# PIC_Microcontroller.net
KiCad netlist of a schematic drawn in Altium Designer
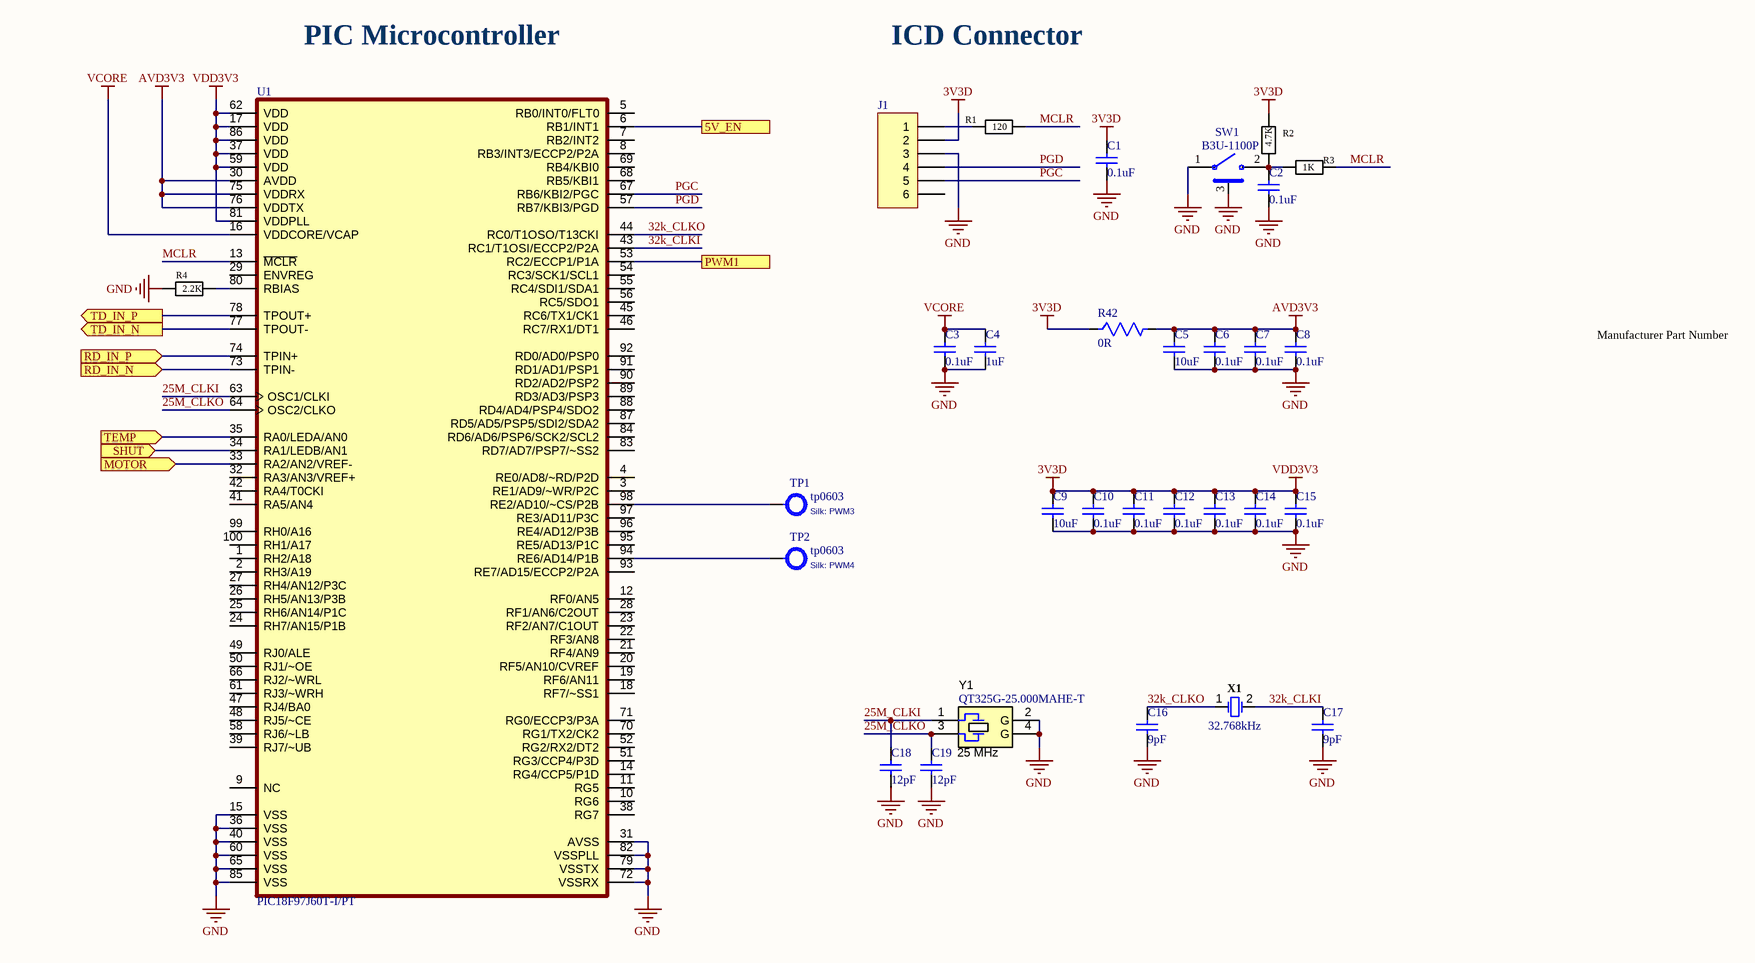
[diagram p0: PIC Microcontroller.SchDoc]

(export (version "E")
  (design (tool "Eeschema 10.0.6"))
  (components
    (comp (ref "C1")
      (value "0.1uF")
      (footprint "CAPC1005X61USR")
      (description "CAP CER 0.1UF 50V X7R 0402")
      (fields
        (field (name "MANUFACTURER") "TDK Corporation")
        (field (name "MANUFACTURER PART NUMBER") "CGA2B3X7R1H104K050BB")
      )
      (libsource (lib "AA-Design-Challenge") (part "Cap"))
    )
    (comp (ref "C2")
      (value "0.1uF")
      (footprint "CAPC1005X61USR")
      (description "CAP CER 0.1UF 50V X7R 0402")
      (fields
        (field (name "MANUFACTURER") "TDK Corporation")
        (field (name "MANUFACTURER PART NUMBER") "CGA2B3X7R1H104K050BB")
      )
      (libsource (lib "AA-Design-Challenge") (part "Cap"))
    )
    (comp (ref "C3")
      (value "0.1uF")
      (footprint "CAPC1005X61USR")
      (description "CAP CER 0.1UF 50V X7R 0402")
      (fields
        (field (name "MANUFACTURER") "TDK Corporation")
        (field (name "MANUFACTURER PART NUMBER") "CGA2B3X7R1H104K050BB")
      )
      (libsource (lib "AA-Design-Challenge") (part "Cap"))
    )
    (comp (ref "C4")
      (value "1uF")
      (footprint "CAPC1005X61USR")
      (description "CAP CER 1UF 16V X5R 0402")
      (fields
        (field (name "MANUFACTURER") "Samsung Electro-Mechanics")
        (field (name "MANUFACTURER PART NUMBER") "CL05A105KO5NNNC")
      )
      (libsource (lib "AA-Design-Challenge") (part "Cap"))
    )
    (comp (ref "C5")
      (value "10uF")
      (footprint "CAPC1005X61USR")
      (description "CAP CER 10UF 10V X5R 0402")
      (fields
        (field (name "MANUFACTURER") "Samsung Electro-Mechanics")
        (field (name "MANUFACTURER PART NUMBER") "CL05A106MP8NUB8")
      )
      (libsource (lib "AA-Design-Challenge") (part "Cap"))
    )
    (comp (ref "C6")
      (value "0.1uF")
      (footprint "CAPC1005X61USR")
      (description "CAP CER 0.1UF 50V X7R 0402")
      (fields
        (field (name "MANUFACTURER") "TDK Corporation")
        (field (name "MANUFACTURER PART NUMBER") "CGA2B3X7R1H104K050BB")
      )
      (libsource (lib "AA-Design-Challenge") (part "Cap"))
    )
    (comp (ref "C7")
      (value "0.1uF")
      (footprint "CAPC1005X61USR")
      (description "CAP CER 0.1UF 50V X7R 0402")
      (fields
        (field (name "MANUFACTURER") "TDK Corporation")
        (field (name "MANUFACTURER PART NUMBER") "CGA2B3X7R1H104K050BB")
      )
      (libsource (lib "AA-Design-Challenge") (part "Cap"))
    )
    (comp (ref "C8")
      (value "0.1uF")
      (footprint "CAPC1005X61USR")
      (description "CAP CER 0.1UF 50V X7R 0402")
      (fields
        (field (name "MANUFACTURER") "TDK Corporation")
        (field (name "MANUFACTURER PART NUMBER") "CGA2B3X7R1H104K050BB")
      )
      (libsource (lib "AA-Design-Challenge") (part "Cap"))
    )
    (comp (ref "C9")
      (value "10uF")
      (footprint "CAPC1005X61USR")
      (description "CAP CER 10UF 10V X5R 0402")
      (fields
        (field (name "MANUFACTURER") "Samsung Electro-Mechanics")
        (field (name "MANUFACTURER PART NUMBER") "CL05A106MP8NUB8")
      )
      (libsource (lib "AA-Design-Challenge") (part "Cap"))
    )
    (comp (ref "C10")
      (value "0.1uF")
      (footprint "CAPC1005X61USR")
      (description "CAP CER 0.1UF 50V X7R 0402")
      (fields
        (field (name "MANUFACTURER") "TDK Corporation")
        (field (name "MANUFACTURER PART NUMBER") "CGA2B3X7R1H104K050BB")
      )
      (libsource (lib "AA-Design-Challenge") (part "Cap"))
    )
    (comp (ref "C11")
      (value "0.1uF")
      (footprint "CAPC1005X61USR")
      (description "CAP CER 0.1UF 50V X7R 0402")
      (fields
        (field (name "MANUFACTURER") "TDK Corporation")
        (field (name "MANUFACTURER PART NUMBER") "CGA2B3X7R1H104K050BB")
      )
      (libsource (lib "AA-Design-Challenge") (part "Cap"))
    )
    (comp (ref "C12")
      (value "0.1uF")
      (footprint "CAPC1005X61USR")
      (description "CAP CER 0.1UF 50V X7R 0402")
      (fields
        (field (name "MANUFACTURER") "TDK Corporation")
        (field (name "MANUFACTURER PART NUMBER") "CGA2B3X7R1H104K050BB")
      )
      (libsource (lib "AA-Design-Challenge") (part "Cap"))
    )
    (comp (ref "C13")
      (value "0.1uF")
      (footprint "CAPC1005X61USR")
      (description "CAP CER 0.1UF 50V X7R 0402")
      (fields
        (field (name "MANUFACTURER") "TDK Corporation")
        (field (name "MANUFACTURER PART NUMBER") "CGA2B3X7R1H104K050BB")
      )
      (libsource (lib "AA-Design-Challenge") (part "Cap"))
    )
    (comp (ref "C14")
      (value "0.1uF")
      (footprint "CAPC1005X61USR")
      (description "CAP CER 0.1UF 50V X7R 0402")
      (fields
        (field (name "MANUFACTURER") "TDK Corporation")
        (field (name "MANUFACTURER PART NUMBER") "CGA2B3X7R1H104K050BB")
      )
      (libsource (lib "AA-Design-Challenge") (part "Cap"))
    )
    (comp (ref "C15")
      (value "0.1uF")
      (footprint "CAPC1005X61USR")
      (description "CAP CER 0.1UF 50V X7R 0402")
      (fields
        (field (name "MANUFACTURER") "TDK Corporation")
        (field (name "MANUFACTURER PART NUMBER") "CGA2B3X7R1H104K050BB")
      )
      (libsource (lib "AA-Design-Challenge") (part "Cap"))
    )
    (comp (ref "C16")
      (value "9pF")
      (footprint "CAPC1005X61USR")
      (description "CAP CER 9PF 50V C0G/NPO 0402")
      (fields
        (field (name "MANUFACTURER") "Yageo")
        (field (name "MANUFACTURER PART NUMBER") "CC0402BRNPO9BN9R0")
      )
      (libsource (lib "AA-Design-Challenge") (part "Cap"))
    )
    (comp (ref "C17")
      (value "9pF")
      (footprint "CAPC1005X61USR")
      (description "CAP CER 9PF 50V C0G/NPO 0402")
      (fields
        (field (name "MANUFACTURER") "Yageo")
        (field (name "MANUFACTURER PART NUMBER") "CC0402BRNPO9BN9R0")
      )
      (libsource (lib "AA-Design-Challenge") (part "Cap"))
    )
    (comp (ref "C18")
      (value "12pF")
      (footprint "CAPC1005X61USR")
      (description "CAP CER 12PF 50V C0G 0402")
      (fields
        (field (name "MANUFACTURER") "TDK Corporation")
        (field (name "MANUFACTURER PART NUMBER") "CGA2B2C0G1H120J050BA")
      )
      (libsource (lib "AA-Design-Challenge") (part "Cap"))
    )
    (comp (ref "C19")
      (value "12pF")
      (footprint "CAPC1005X61USR")
      (description "CAP CER 12PF 50V C0G 0402")
      (fields
        (field (name "MANUFACTURER") "TDK Corporation")
        (field (name "MANUFACTURER PART NUMBER") "CGA2B2C0G1H120J050BA")
      )
      (libsource (lib "AA-Design-Challenge") (part "Cap"))
    )
    (comp (ref "J1")
      (value "Header 6")
      (footprint "HDR1X6")
      (description "Header, 6-Pin")
      (fields (field (name "PUBLISHER") "Altium Limited"))
      (libsource (lib "AA-Design-Challenge") (part "Header 6"))
    )
    (comp (ref "R1")
      (value "120")
      (footprint "RESC1005X40USR")
      (description "RES SMD 120 OHM 1% 1/16W 0402")
      (fields
        (field (name "MANUFACTURER") "Yageo")
        (field (name "MANUFACTURER PART NUMBER") "RC0402FR-07120RL")
      )
      (libsource (lib "AA-Design-Challenge") (part "R"))
    )
    (comp (ref "R2")
      (value "4.7K")
      (footprint "RESC1005X40USR")
      (description "RES SMD 4.7K OHM 1% 1/16W 0402")
      (fields
        (field (name "MANUFACTURER") "Yageo")
        (field (name "MANUFACTURER PART NUMBER") "RC0402FR-074K7L")
      )
      (libsource (lib "") (part "R_1"))
    )
    (comp (ref "R3")
      (value "1K")
      (footprint "RESC1005X40USR")
      (description "RES SMD 1K OHM 1% 1/16W 0402")
      (fields
        (field (name "MANUFACTURER") "Yageo")
        (field (name "MANUFACTURER PART NUMBER") "RC0402FR-071KL")
      )
      (libsource (lib "AA-Design-Challenge") (part "R"))
    )
    (comp (ref "R4")
      (value "2.2K")
      (footprint "RESC1005X40USR")
      (description "RES SMD 2.2K OHM 1% 1/16W 0402")
      (fields
        (field (name "MANUFACTURER") "Yageo")
        (field (name "MANUFACTURER PART NUMBER") "RC0402FR-072K2L")
      )
      (libsource (lib "AA-Design-Challenge") (part "R"))
    )
    (comp (ref "R42")
      (value "0R")
      (footprint "R_0603")
      (description "Fixed Resistor, Metal Glaze/thick Film, 0.1W, 0ohm, Surface Mount, 0603")
      (fields
        (field (name "MANUFACTURER") "Yageo")
        (field (name "MANUFACTURER PART NUMBER") "RC0603FR-070RL")
      )
      (libsource (lib "OP_Library") (part "Res 0R 1/10W 0603"))
    )
    (comp (ref "SW1")
      (value "B3U-1100P")
      (footprint "SW_B3U-1100P")
      (description "SWITCH TACTILE SPST-NO 0.05A 12V")
      (fields (field (name "MANUFACTURER") "Omron"))
      (libsource (lib "AA-Design-Challenge") (part "B3U-1100P"))
    )
    (comp (ref "TP1")
      (value "tp0603")
      (footprint "TP 1mm")
      (fields (field (name "SILK") "PWM3") (field (name "PART NUMBER") "4001364"))
      (libsource (lib "AA-Design-Challenge") (part "Testpkt0603"))
    )
    (comp (ref "TP2")
      (value "tp0603")
      (footprint "TP 1mm")
      (fields (field (name "SILK") "PWM4") (field (name "PART NUMBER") "4001364"))
      (libsource (lib "AA-Design-Challenge") (part "Testpkt0603"))
    )
    (comp (ref "U1")
      (value "PIC18F97J60T-I/PT")
      (footprint "QFP40P1400X1400X120-100N")
      (description "IC MCU 8BIT 128KB FLASH 100TQFP (12x12)")
      (fields
        (field (name "DIGI-KEY PART NUMBER") "PIC18F97J60T-I/PTTR-ND")
        (field (name "MANUFACTURER") "Microchip")
      )
      (libsource (lib "AA-Design-Challenge") (part "PIC18F97J60T-I/PT"))
    )
    (comp (ref "X1")
      (value "32.768kHz")
      (footprint "XTAL_3215")
      (description "CRYSTAL 32.7680KHZ 9PF SMD")
      (fields
        (field (name "MANUFACTURER") "EPSON")
        (field (name "MANUFACTURER PART NUMBER") "FC-135 32.7680KA-AC0")
      )
      (libsource (lib "AA-Design-Challenge") (part "XTAL-1-2-2"))
    )
    (comp (ref "Y1")
      (value "QT325G-25.000MAHE-T")
      (footprint "XTAL_3225")
      (description "CRYSTAL 25.0000MHZ 12PF SMD")
      (fields (field (name "FREQUENCY_FIXED") "25 MHz") (field (name "MANUFACTURER") "QST"))
      (libsource (lib "AA-Design-Challenge") (part "ABM8AIG-25.000MHZ-12-2Z-T3"))
    )
  )
  (nets
    (net (code "1") (name "/5V_EN") (class "Default")
      (node (ref "U1") (pin "6") (pinfunction "RB1/INT1_6") (pintype "passive"))
    )
    (net (code "2") (name "/25M_CLKI") (class "Default")
      (node (ref "C18") (pin "1") (pinfunction "1_1") (pintype "passive"))
      (node (ref "U1") (pin "63") (pinfunction "OSC1/CLKI_63") (pintype "passive"))
      (node (ref "Y1") (pin "1") (pinfunction "1_1") (pintype "passive"))
    )
    (net (code "3") (name "/25M_CLKO") (class "Default")
      (node (ref "C19") (pin "1") (pinfunction "1_1") (pintype "passive"))
      (node (ref "U1") (pin "64") (pinfunction "OSC2/CLKO_64") (pintype "passive"))
      (node (ref "Y1") (pin "3") (pinfunction "3_3") (pintype "passive"))
    )
    (net (code "4") (name "/32k_CLKI") (class "Default")
      (node (ref "C17") (pin "1") (pinfunction "1_1") (pintype "passive"))
      (node (ref "U1") (pin "43") (pinfunction "RC1/T1OSI/ECCP2/P2A_43") (pintype "passive"))
      (node (ref "X1") (pin "2") (pinfunction "2_2") (pintype "passive"))
    )
    (net (code "5") (name "/32k_CLKO") (class "Default")
      (node (ref "C16") (pin "1") (pinfunction "1_1") (pintype "passive"))
      (node (ref "U1") (pin "44") (pinfunction "RC0/T1OSO/T13CKI_44") (pintype "passive"))
      (node (ref "X1") (pin "1") (pinfunction "1_1") (pintype "passive"))
    )
    (net (code "6") (name "/MCLR") (class "Default")
      (node (ref "R1") (pin "2") (pintype "passive"))
      (node (ref "R3") (pin "2") (pintype "passive"))
      (node (ref "U1") (pin "13") (pinfunction "~{MCLR}_13") (pintype "passive"))
    )
    (net (code "7") (name "/MOTOR") (class "Default")
      (node (ref "U1") (pin "33") (pinfunction "RA2/AN2/VREF-_33") (pintype "passive"))
    )
    (net (code "8") (name "/PGC") (class "Default")
      (node (ref "J1") (pin "5") (pinfunction "5_5") (pintype "passive"))
      (node (ref "U1") (pin "67") (pinfunction "RB6/KBI2/PGC_67") (pintype "passive"))
    )
    (net (code "9") (name "/PGD") (class "Default")
      (node (ref "J1") (pin "4") (pinfunction "4_4") (pintype "passive"))
      (node (ref "U1") (pin "57") (pinfunction "RB7/KBI3/PGD_57") (pintype "passive"))
    )
    (net (code "10") (name "/PWM1") (class "Default")
      (node (ref "U1") (pin "53") (pinfunction "RC2/ECCP1/P1A_53") (pintype "passive"))
    )
    (net (code "11") (name "/RD_IN_N") (class "Default")
      (node (ref "U1") (pin "73") (pinfunction "TPIN-_73") (pintype "passive"))
    )
    (net (code "12") (name "/RD_IN_P") (class "Default")
      (node (ref "U1") (pin "74") (pinfunction "TPIN+_74") (pintype "passive"))
    )
    (net (code "13") (name "/SHUT") (class "Default")
      (node (ref "U1") (pin "34") (pinfunction "RA1/LEDB/AN1_34") (pintype "passive"))
    )
    (net (code "14") (name "/TD_IN_N") (class "Default")
      (node (ref "U1") (pin "77") (pinfunction "TPOUT-_77") (pintype "passive"))
    )
    (net (code "15") (name "/TD_IN_P") (class "Default")
      (node (ref "U1") (pin "78") (pinfunction "TPOUT+_78") (pintype "passive"))
    )
    (net (code "16") (name "/TEMP") (class "Default")
      (node (ref "U1") (pin "35") (pinfunction "RA0/LEDA/AN0_35") (pintype "passive"))
    )
    (net (code "17") (name "3V3D") (class "Default")
      (node (ref "C1") (pin "1") (pinfunction "1_1") (pintype "passive"))
      (node (ref "C10") (pin "1") (pinfunction "1_1") (pintype "passive"))
      (node (ref "C11") (pin "1") (pinfunction "1_1") (pintype "passive"))
      (node (ref "C12") (pin "1") (pinfunction "1_1") (pintype "passive"))
      (node (ref "C13") (pin "1") (pinfunction "1_1") (pintype "passive"))
      (node (ref "C14") (pin "1") (pinfunction "1_1") (pintype "passive"))
      (node (ref "C15") (pin "1") (pinfunction "1_1") (pintype "passive"))
      (node (ref "C9") (pin "1") (pinfunction "1_1") (pintype "passive"))
      (node (ref "J1") (pin "2") (pinfunction "2_2") (pintype "passive"))
      (node (ref "R2") (pin "1") (pintype "passive"))
      (node (ref "R42") (pin "1") (pinfunction "1_1") (pintype "passive"))
      (node (ref "U1") (pin "17") (pinfunction "VDD_17") (pintype "passive"))
      (node (ref "U1") (pin "37") (pinfunction "VDD_37") (pintype "passive"))
      (node (ref "U1") (pin "59") (pinfunction "VDD_59") (pintype "passive"))
      (node (ref "U1") (pin "62") (pinfunction "VDD_62") (pintype "passive"))
      (node (ref "U1") (pin "81") (pinfunction "VDDPLL_81") (pintype "passive"))
      (node (ref "U1") (pin "86") (pinfunction "VDD_86") (pintype "passive"))
    )
    (net (code "18") (name "AVD3V3") (class "Default")
      (node (ref "C5") (pin "1") (pinfunction "1_1") (pintype "passive"))
      (node (ref "C6") (pin "1") (pinfunction "1_1") (pintype "passive"))
      (node (ref "C7") (pin "1") (pinfunction "1_1") (pintype "passive"))
      (node (ref "C8") (pin "1") (pinfunction "1_1") (pintype "passive"))
      (node (ref "R42") (pin "2") (pinfunction "2_2") (pintype "passive"))
      (node (ref "U1") (pin "30") (pinfunction "AVDD_30") (pintype "passive"))
      (node (ref "U1") (pin "75") (pinfunction "VDDRX_75") (pintype "passive"))
      (node (ref "U1") (pin "76") (pinfunction "VDDTX_76") (pintype "passive"))
    )
    (net (code "19") (name "GND") (class "Default")
      (node (ref "C1") (pin "2") (pinfunction "2_2") (pintype "passive"))
      (node (ref "C10") (pin "2") (pinfunction "2_2") (pintype "passive"))
      (node (ref "C11") (pin "2") (pinfunction "2_2") (pintype "passive"))
      (node (ref "C12") (pin "2") (pinfunction "2_2") (pintype "passive"))
      (node (ref "C13") (pin "2") (pinfunction "2_2") (pintype "passive"))
      (node (ref "C14") (pin "2") (pinfunction "2_2") (pintype "passive"))
      (node (ref "C15") (pin "2") (pinfunction "2_2") (pintype "passive"))
      (node (ref "C16") (pin "2") (pinfunction "2_2") (pintype "passive"))
      (node (ref "C17") (pin "2") (pinfunction "2_2") (pintype "passive"))
      (node (ref "C18") (pin "2") (pinfunction "2_2") (pintype "passive"))
      (node (ref "C19") (pin "2") (pinfunction "2_2") (pintype "passive"))
      (node (ref "C2") (pin "2") (pinfunction "2_2") (pintype "passive"))
      (node (ref "C3") (pin "2") (pinfunction "2_2") (pintype "passive"))
      (node (ref "C4") (pin "1") (pinfunction "1_1") (pintype "passive"))
      (node (ref "C5") (pin "2") (pinfunction "2_2") (pintype "passive"))
      (node (ref "C6") (pin "2") (pinfunction "2_2") (pintype "passive"))
      (node (ref "C7") (pin "2") (pinfunction "2_2") (pintype "passive"))
      (node (ref "C8") (pin "2") (pinfunction "2_2") (pintype "passive"))
      (node (ref "C9") (pin "2") (pinfunction "2_2") (pintype "passive"))
      (node (ref "J1") (pin "3") (pinfunction "3_3") (pintype "passive"))
      (node (ref "R4") (pin "1") (pintype "passive"))
      (node (ref "SW1") (pin "1") (pinfunction "1_1") (pintype "passive"))
      (node (ref "SW1") (pin "3") (pinfunction "3_3") (pintype "passive"))
      (node (ref "U1") (pin "15") (pinfunction "VSS_15") (pintype "passive"))
      (node (ref "U1") (pin "31") (pinfunction "AVSS_31") (pintype "passive"))
      (node (ref "U1") (pin "36") (pinfunction "VSS_36") (pintype "passive"))
      (node (ref "U1") (pin "40") (pinfunction "VSS_40") (pintype "passive"))
      (node (ref "U1") (pin "60") (pinfunction "VSS_60") (pintype "passive"))
      (node (ref "U1") (pin "65") (pinfunction "VSS_65") (pintype "passive"))
      (node (ref "U1") (pin "72") (pinfunction "VSSRX_72") (pintype "passive"))
      (node (ref "U1") (pin "79") (pinfunction "VSSTX_79") (pintype "passive"))
      (node (ref "U1") (pin "82") (pinfunction "VSSPLL_82") (pintype "passive"))
      (node (ref "U1") (pin "85") (pinfunction "VSS_85") (pintype "passive"))
      (node (ref "Y1") (pin "2") (pinfunction "GND_2") (pintype "power_in"))
      (node (ref "Y1") (pin "4") (pinfunction "GND_4") (pintype "power_in"))
    )
    (net (code "20") (name "Net-(C2-Pad1)") (class "Default")
      (node (ref "C2") (pin "1") (pinfunction "1_1") (pintype "passive"))
      (node (ref "R2") (pin "2") (pintype "passive"))
      (node (ref "R3") (pin "1") (pintype "passive"))
      (node (ref "SW1") (pin "2") (pinfunction "2_2") (pintype "passive"))
    )
    (net (code "21") (name "Net-(J1-Pad1)") (class "Default")
      (node (ref "J1") (pin "1") (pinfunction "1_1") (pintype "passive"))
      (node (ref "R1") (pin "1") (pintype "passive"))
    )
    (net (code "22") (name "Net-(U1-RBIAS)") (class "Default")
      (node (ref "R4") (pin "2") (pintype "passive"))
      (node (ref "U1") (pin "80") (pinfunction "RBIAS_80") (pintype "passive"))
    )
    (net (code "23") (name "Net-(U1-RE2{slash}AD10{slash}~CS{slash}P2B)") (class "Default")
      (node (ref "TP1") (pin "1") (pinfunction "1_1") (pintype "passive"))
      (node (ref "U1") (pin "98") (pinfunction "RE2/AD10/~CS/P2B_98") (pintype "passive"))
    )
    (net (code "24") (name "Net-(U1-RE6{slash}AD14{slash}P1B)") (class "Default")
      (node (ref "TP2") (pin "1") (pinfunction "1_1") (pintype "passive"))
      (node (ref "U1") (pin "94") (pinfunction "RE6/AD14/P1B_94") (pintype "passive"))
    )
    (net (code "25") (name "VCORE") (class "Default")
      (node (ref "C3") (pin "1") (pinfunction "1_1") (pintype "passive"))
      (node (ref "C4") (pin "2") (pinfunction "2_2") (pintype "passive"))
      (node (ref "U1") (pin "16") (pinfunction "VDDCORE/VCAP_16") (pintype "passive"))
    )
    (net (code "26") (name "unconnected-(J1-Pad6)") (class "Default")
      (node (ref "J1") (pin "6") (pinfunction "6_6") (pintype "passive"))
    )
    (net (code "27") (name "unconnected-(U1-ENVREG-Pad29)") (class "Default")
      (node (ref "U1") (pin "29") (pinfunction "ENVREG_29") (pintype "passive"))
    )
    (net (code "28") (name "unconnected-(U1-NC-Pad9)") (class "Default")
      (node (ref "U1") (pin "9") (pinfunction "NC_9") (pintype "passive"))
    )
    (net (code "29") (name "unconnected-(U1-RA3{slash}AN3{slash}VREF+-Pad32)") (class "Default")
      (node (ref "U1") (pin "32") (pinfunction "RA3/AN3/VREF+_32") (pintype "passive"))
    )
    (net (code "30") (name "unconnected-(U1-RA4{slash}T0CKI-Pad42)") (class "Default")
      (node (ref "U1") (pin "42") (pinfunction "RA4/T0CKI_42") (pintype "passive"))
    )
    (net (code "31") (name "unconnected-(U1-RA5{slash}AN4-Pad41)") (class "Default")
      (node (ref "U1") (pin "41") (pinfunction "RA5/AN4_41") (pintype "passive"))
    )
    (net (code "32") (name "unconnected-(U1-RB0{slash}INT0{slash}FLT0-Pad5)") (class "Default")
      (node (ref "U1") (pin "5") (pinfunction "RB0/INT0/FLT0_5") (pintype "passive"))
    )
    (net (code "33") (name "unconnected-(U1-RB2{slash}INT2-Pad7)") (class "Default")
      (node (ref "U1") (pin "7") (pinfunction "RB2/INT2_7") (pintype "passive"))
    )
    (net (code "34") (name "unconnected-(U1-RB3{slash}INT3{slash}ECCP2{slash}P2A-Pad8)") (class "Default")
      (node (ref "U1") (pin "8") (pinfunction "RB3/INT3/ECCP2/P2A_8") (pintype "passive"))
    )
    (net (code "35") (name "unconnected-(U1-RB4{slash}KBI0-Pad69)") (class "Default")
      (node (ref "U1") (pin "69") (pinfunction "RB4/KBI0_69") (pintype "passive"))
    )
    (net (code "36") (name "unconnected-(U1-RB5{slash}KBI1-Pad68)") (class "Default")
      (node (ref "U1") (pin "68") (pinfunction "RB5/KBI1_68") (pintype "passive"))
    )
    (net (code "37") (name "unconnected-(U1-RC3{slash}SCK1{slash}SCL1-Pad54)") (class "Default")
      (node (ref "U1") (pin "54") (pinfunction "RC3/SCK1/SCL1_54") (pintype "passive"))
    )
    (net (code "38") (name "unconnected-(U1-RC4{slash}SDI1{slash}SDA1-Pad55)") (class "Default")
      (node (ref "U1") (pin "55") (pinfunction "RC4/SDI1/SDA1_55") (pintype "passive"))
    )
    (net (code "39") (name "unconnected-(U1-RC5{slash}SDO1-Pad56)") (class "Default")
      (node (ref "U1") (pin "56") (pinfunction "RC5/SDO1_56") (pintype "passive"))
    )
    (net (code "40") (name "unconnected-(U1-RC6{slash}TX1{slash}CK1-Pad45)") (class "Default")
      (node (ref "U1") (pin "45") (pinfunction "RC6/TX1/CK1_45") (pintype "passive"))
    )
    (net (code "41") (name "unconnected-(U1-RC7{slash}RX1{slash}DT1-Pad46)") (class "Default")
      (node (ref "U1") (pin "46") (pinfunction "RC7/RX1/DT1_46") (pintype "passive"))
    )
    (net (code "42") (name "unconnected-(U1-RD0{slash}AD0{slash}PSP0-Pad92)") (class "Default")
      (node (ref "U1") (pin "92") (pinfunction "RD0/AD0/PSP0_92") (pintype "passive"))
    )
    (net (code "43") (name "unconnected-(U1-RD1{slash}AD1{slash}PSP1-Pad91)") (class "Default")
      (node (ref "U1") (pin "91") (pinfunction "RD1/AD1/PSP1_91") (pintype "passive"))
    )
    (net (code "44") (name "unconnected-(U1-RD2{slash}AD2{slash}PSP2-Pad90)") (class "Default")
      (node (ref "U1") (pin "90") (pinfunction "RD2/AD2/PSP2_90") (pintype "passive"))
    )
    (net (code "45") (name "unconnected-(U1-RD3{slash}AD3{slash}PSP3-Pad89)") (class "Default")
      (node (ref "U1") (pin "89") (pinfunction "RD3/AD3/PSP3_89") (pintype "passive"))
    )
    (net (code "46") (name "unconnected-(U1-RD4{slash}AD4{slash}PSP4{slash}SDO2-Pad88)") (class "Default")
      (node (ref "U1") (pin "88") (pinfunction "RD4/AD4/PSP4/SDO2_88") (pintype "passive"))
    )
    (net (code "47") (name "unconnected-(U1-RD5{slash}AD5{slash}PSP5{slash}SDI2{slash}SDA2-Pad87)") (class "Default")
      (node (ref "U1") (pin "87") (pinfunction "RD5/AD5/PSP5/SDI2/SDA2_87") (pintype "passive"))
    )
    (net (code "48") (name "unconnected-(U1-RD6{slash}AD6{slash}PSP6{slash}SCK2{slash}SCL2-Pad84)") (class "Default")
      (node (ref "U1") (pin "84") (pinfunction "RD6/AD6/PSP6/SCK2/SCL2_84") (pintype "passive"))
    )
    (net (code "49") (name "unconnected-(U1-RD7{slash}AD7{slash}PSP7{slash}~SS2-Pad83)") (class "Default")
      (node (ref "U1") (pin "83") (pinfunction "RD7/AD7/PSP7/~SS2_83") (pintype "passive"))
    )
    (net (code "50") (name "unconnected-(U1-RE0{slash}AD8{slash}~RD{slash}P2D-Pad4)") (class "Default")
      (node (ref "U1") (pin "4") (pinfunction "RE0/AD8/~RD/P2D_4") (pintype "passive"))
    )
    (net (code "51") (name "unconnected-(U1-RE1{slash}AD9{slash}~WR{slash}P2C-Pad3)") (class "Default")
      (node (ref "U1") (pin "3") (pinfunction "RE1/AD9/~WR/P2C_3") (pintype "passive"))
    )
    (net (code "52") (name "unconnected-(U1-RE3{slash}AD11{slash}P3C-Pad97)") (class "Default")
      (node (ref "U1") (pin "97") (pinfunction "RE3/AD11/P3C_97") (pintype "passive"))
    )
    (net (code "53") (name "unconnected-(U1-RE4{slash}AD12{slash}P3B-Pad96)") (class "Default")
      (node (ref "U1") (pin "96") (pinfunction "RE4/AD12/P3B_96") (pintype "passive"))
    )
    (net (code "54") (name "unconnected-(U1-RE5{slash}AD13{slash}P1C-Pad95)") (class "Default")
      (node (ref "U1") (pin "95") (pinfunction "RE5/AD13/P1C_95") (pintype "passive"))
    )
    (net (code "55") (name "unconnected-(U1-RE7{slash}AD15{slash}ECCP2{slash}P2A-Pad93)") (class "Default")
      (node (ref "U1") (pin "93") (pinfunction "RE7/AD15/ECCP2/P2A_93") (pintype "passive"))
    )
    (net (code "56") (name "unconnected-(U1-RF0{slash}AN5-Pad12)") (class "Default")
      (node (ref "U1") (pin "12") (pinfunction "RF0/AN5_12") (pintype "passive"))
    )
    (net (code "57") (name "unconnected-(U1-RF1{slash}AN6{slash}C2OUT-Pad28)") (class "Default")
      (node (ref "U1") (pin "28") (pinfunction "RF1/AN6/C2OUT_28") (pintype "passive"))
    )
    (net (code "58") (name "unconnected-(U1-RF2{slash}AN7{slash}C1OUT-Pad23)") (class "Default")
      (node (ref "U1") (pin "23") (pinfunction "RF2/AN7/C1OUT_23") (pintype "passive"))
    )
    (net (code "59") (name "unconnected-(U1-RF3{slash}AN8-Pad22)") (class "Default")
      (node (ref "U1") (pin "22") (pinfunction "RF3/AN8_22") (pintype "passive"))
    )
    (net (code "60") (name "unconnected-(U1-RF4{slash}AN9-Pad21)") (class "Default")
      (node (ref "U1") (pin "21") (pinfunction "RF4/AN9_21") (pintype "passive"))
    )
    (net (code "61") (name "unconnected-(U1-RF5{slash}AN10{slash}CVREF-Pad20)") (class "Default")
      (node (ref "U1") (pin "20") (pinfunction "RF5/AN10/CVREF_20") (pintype "passive"))
    )
    (net (code "62") (name "unconnected-(U1-RF6{slash}AN11-Pad19)") (class "Default")
      (node (ref "U1") (pin "19") (pinfunction "RF6/AN11_19") (pintype "passive"))
    )
    (net (code "63") (name "unconnected-(U1-RF7{slash}~SS1-Pad18)") (class "Default")
      (node (ref "U1") (pin "18") (pinfunction "RF7/~SS1_18") (pintype "passive"))
    )
    (net (code "64") (name "unconnected-(U1-RG0{slash}ECCP3{slash}P3A-Pad71)") (class "Default")
      (node (ref "U1") (pin "71") (pinfunction "RG0/ECCP3/P3A_71") (pintype "passive"))
    )
    (net (code "65") (name "unconnected-(U1-RG1{slash}TX2{slash}CK2-Pad70)") (class "Default")
      (node (ref "U1") (pin "70") (pinfunction "RG1/TX2/CK2_70") (pintype "passive"))
    )
    (net (code "66") (name "unconnected-(U1-RG2{slash}RX2{slash}DT2-Pad52)") (class "Default")
      (node (ref "U1") (pin "52") (pinfunction "RG2/RX2/DT2_52") (pintype "passive"))
    )
    (net (code "67") (name "unconnected-(U1-RG3{slash}CCP4{slash}P3D-Pad51)") (class "Default")
      (node (ref "U1") (pin "51") (pinfunction "RG3/CCP4/P3D_51") (pintype "passive"))
    )
    (net (code "68") (name "unconnected-(U1-RG4{slash}CCP5{slash}P1D-Pad14)") (class "Default")
      (node (ref "U1") (pin "14") (pinfunction "RG4/CCP5/P1D_14") (pintype "passive"))
    )
    (net (code "69") (name "unconnected-(U1-RG5-Pad11)") (class "Default")
      (node (ref "U1") (pin "11") (pinfunction "RG5_11") (pintype "passive"))
    )
    (net (code "70") (name "unconnected-(U1-RG6-Pad10)") (class "Default")
      (node (ref "U1") (pin "10") (pinfunction "RG6_10") (pintype "passive"))
    )
    (net (code "71") (name "unconnected-(U1-RG7-Pad38)") (class "Default")
      (node (ref "U1") (pin "38") (pinfunction "RG7_38") (pintype "passive"))
    )
    (net (code "72") (name "unconnected-(U1-RH0{slash}A16-Pad99)") (class "Default")
      (node (ref "U1") (pin "99") (pinfunction "RH0/A16_99") (pintype "passive"))
    )
    (net (code "73") (name "unconnected-(U1-RH1{slash}A17-Pad100)") (class "Default")
      (node (ref "U1") (pin "100") (pinfunction "RH1/A17_100") (pintype "passive"))
    )
    (net (code "74") (name "unconnected-(U1-RH2{slash}A18-Pad1)") (class "Default")
      (node (ref "U1") (pin "1") (pinfunction "RH2/A18_1") (pintype "passive"))
    )
    (net (code "75") (name "unconnected-(U1-RH3{slash}A19-Pad2)") (class "Default")
      (node (ref "U1") (pin "2") (pinfunction "RH3/A19_2") (pintype "passive"))
    )
    (net (code "76") (name "unconnected-(U1-RH4{slash}AN12{slash}P3C-Pad27)") (class "Default")
      (node (ref "U1") (pin "27") (pinfunction "RH4/AN12/P3C_27") (pintype "passive"))
    )
    (net (code "77") (name "unconnected-(U1-RH5{slash}AN13{slash}P3B-Pad26)") (class "Default")
      (node (ref "U1") (pin "26") (pinfunction "RH5/AN13/P3B_26") (pintype "passive"))
    )
    (net (code "78") (name "unconnected-(U1-RH6{slash}AN14{slash}P1C-Pad25)") (class "Default")
      (node (ref "U1") (pin "25") (pinfunction "RH6/AN14/P1C_25") (pintype "passive"))
    )
    (net (code "79") (name "unconnected-(U1-RH7{slash}AN15{slash}P1B-Pad24)") (class "Default")
      (node (ref "U1") (pin "24") (pinfunction "RH7/AN15/P1B_24") (pintype "passive"))
    )
    (net (code "80") (name "unconnected-(U1-RJ0{slash}ALE-Pad49)") (class "Default")
      (node (ref "U1") (pin "49") (pinfunction "RJ0/ALE_49") (pintype "passive"))
    )
    (net (code "81") (name "unconnected-(U1-RJ1{slash}~OE-Pad50)") (class "Default")
      (node (ref "U1") (pin "50") (pinfunction "RJ1/~OE_50") (pintype "passive"))
    )
    (net (code "82") (name "unconnected-(U1-RJ2{slash}~WRL-Pad66)") (class "Default")
      (node (ref "U1") (pin "66") (pinfunction "RJ2/~WRL_66") (pintype "passive"))
    )
    (net (code "83") (name "unconnected-(U1-RJ3{slash}~WRH-Pad61)") (class "Default")
      (node (ref "U1") (pin "61") (pinfunction "RJ3/~WRH_61") (pintype "passive"))
    )
    (net (code "84") (name "unconnected-(U1-RJ4{slash}BA0-Pad47)") (class "Default")
      (node (ref "U1") (pin "47") (pinfunction "RJ4/BA0_47") (pintype "passive"))
    )
    (net (code "85") (name "unconnected-(U1-RJ5{slash}~CE-Pad48)") (class "Default")
      (node (ref "U1") (pin "48") (pinfunction "RJ5/~CE_48") (pintype "passive"))
    )
    (net (code "86") (name "unconnected-(U1-RJ6{slash}~LB-Pad58)") (class "Default")
      (node (ref "U1") (pin "58") (pinfunction "RJ6/~LB_58") (pintype "passive"))
    )
    (net (code "87") (name "unconnected-(U1-RJ7{slash}~UB-Pad39)") (class "Default")
      (node (ref "U1") (pin "39") (pinfunction "RJ7/~UB_39") (pintype "passive"))
    )
  )
)
